# blink1mk3_micro1c.net
KiCad netlist of a schematic drawn in EAGLE
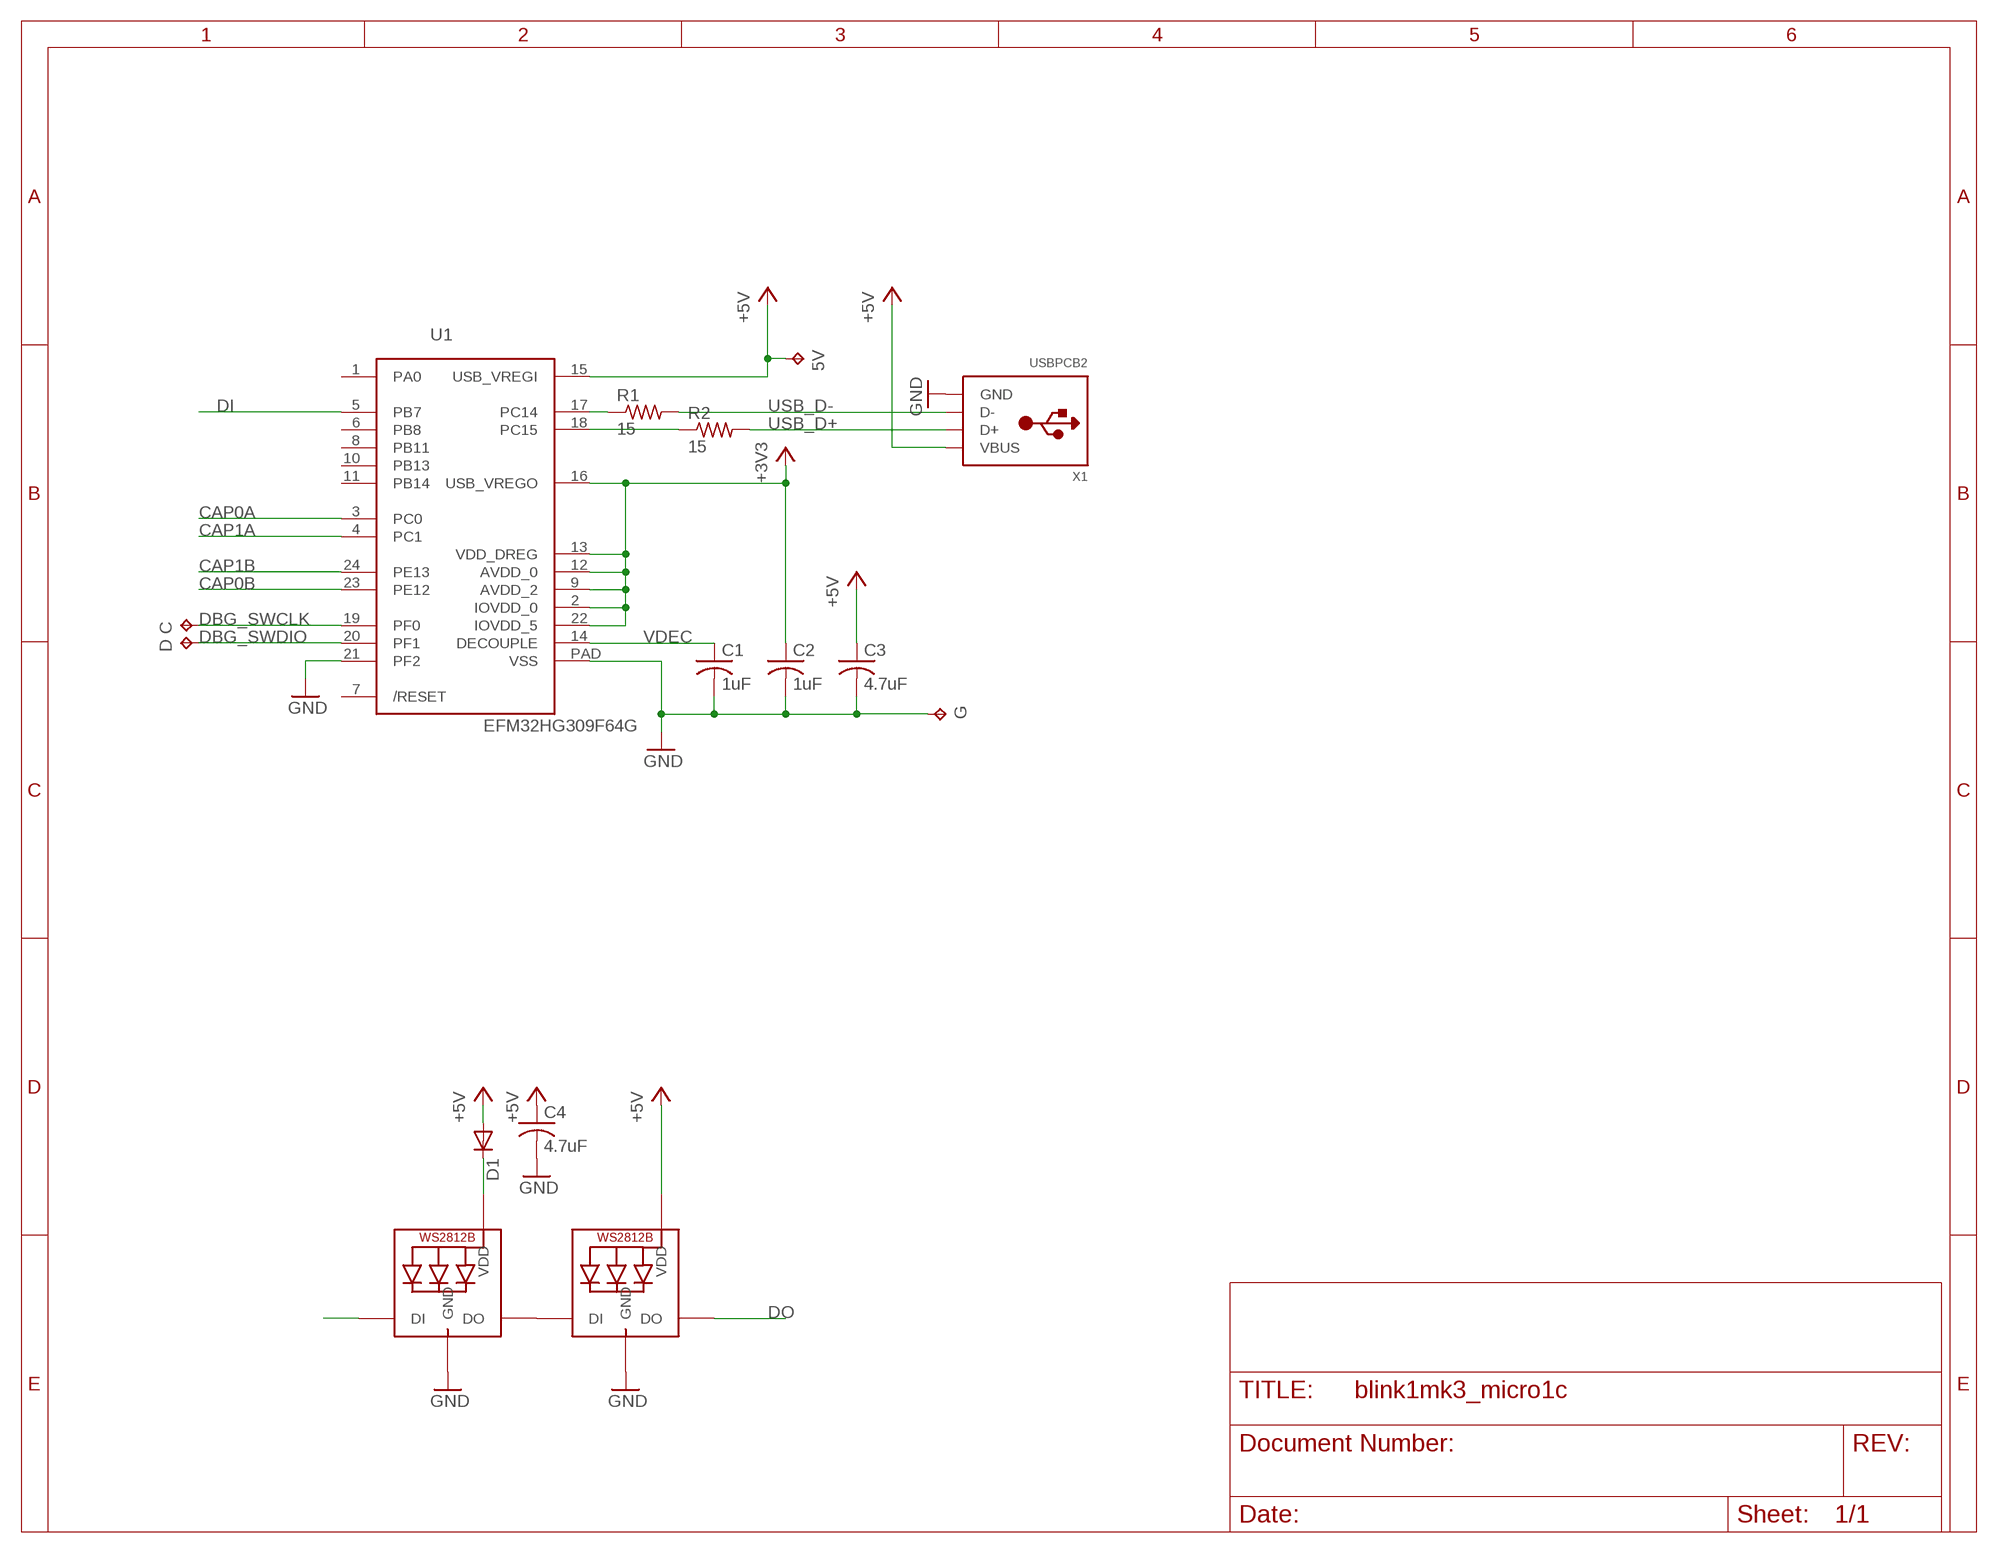
[diagram p0: schematic, sheet 1]

(export (version "E")
  (design (tool "Eeschema 10.0.6"))
  (components
    (comp (ref "5V")
      (value "TPTP10R")
      (footprint "eagle-import:TP10R")
      (libsource (lib "eagle-import") (part "TPTP10R"))
    )
    (comp (ref "C")
      (value "TPTP10R")
      (footprint "eagle-import:TP10R")
      (libsource (lib "eagle-import") (part "TPTP10R"))
    )
    (comp (ref "C1")
      (value "1uF")
      (footprint "eagle-import:C0402")
      (libsource (lib "eagle-import") (part "C-USC0402"))
    )
    (comp (ref "C2")
      (value "1uF")
      (footprint "eagle-import:C0402")
      (libsource (lib "eagle-import") (part "C-USC0402"))
    )
    (comp (ref "C3")
      (value "4.7uF")
      (footprint "eagle-import:C0402")
      (libsource (lib "eagle-import") (part "C-USC0402"))
    )
    (comp (ref "C4")
      (value "4.7uF")
      (footprint "eagle-import:C0402")
      (libsource (lib "eagle-import") (part "C-USC0402"))
    )
    (comp (ref "D")
      (value "TPTP10R")
      (footprint "eagle-import:TP10R")
      (libsource (lib "eagle-import") (part "TPTP10R"))
    )
    (comp (ref "D1")
      (value "DIODE-SOD523")
      (footprint "eagle-import:SOD523")
      (libsource (lib "eagle-import") (part "DIODE-SOD523"))
    )
    (comp (ref "G")
      (value "TPTP10SQ")
      (footprint "eagle-import:TP10SQ")
      (libsource (lib "eagle-import") (part "TPTP10SQ"))
    )
    (comp (ref "LED1")
      (value "WS2812B4020SIDE")
      (footprint "eagle-import:SK6812-SIDE")
      (libsource (lib "eagle-import") (part "WS2812B4020SIDE"))
    )
    (comp (ref "LED2")
      (value "WS2812B4020SIDE")
      (footprint "eagle-import:SK6812-SIDE")
      (libsource (lib "eagle-import") (part "WS2812B4020SIDE"))
    )
    (comp (ref "R1")
      (value "15")
      (footprint "eagle-import:R0402")
      (libsource (lib "eagle-import") (part "R-US_R0402"))
    )
    (comp (ref "R2")
      (value "15")
      (footprint "eagle-import:R0402")
      (libsource (lib "eagle-import") (part "R-US_R0402"))
    )
    (comp (ref "U1")
      (value "EFM32HG309F64G")
      (footprint "eagle-import:QFN24PAD")
      (libsource (lib "eagle-import") (part "EFM32HG309F64G"))
    )
    (comp (ref "X1")
      (value "USBPCB2")
      (footprint "eagle-import:USB-A-PCB-2")
      (libsource (lib "eagle-import") (part "USBPCB2"))
    )
  )
  (nets
    (net (code "1") (name "+3V3") (class "Default")
      (node (ref "C2") (pin "1") (pinfunction "1_1") (pintype "passive"))
      (node (ref "U1") (pin "12") (pinfunction "AVDD_0_12") (pintype "bidirectional"))
      (node (ref "U1") (pin "13") (pinfunction "VDD_DREG_13") (pintype "bidirectional"))
      (node (ref "U1") (pin "16") (pinfunction "USB_VREGO_16") (pintype "bidirectional"))
      (node (ref "U1") (pin "2") (pinfunction "IOVDD_0_2") (pintype "bidirectional"))
      (node (ref "U1") (pin "22") (pinfunction "IOVDD_5_22") (pintype "bidirectional"))
      (node (ref "U1") (pin "9") (pinfunction "AVDD_2_9") (pintype "bidirectional"))
    )
    (net (code "2") (name "+5V") (class "Default")
      (node (ref "5V") (pin "TP") (pinfunction "TP_TP") (pintype "input"))
      (node (ref "C3") (pin "1") (pinfunction "1_1") (pintype "passive"))
      (node (ref "C4") (pin "1") (pinfunction "1_1") (pintype "passive"))
      (node (ref "D1") (pin "A") (pinfunction "A_A") (pintype "passive"))
      (node (ref "LED2") (pin "1-VDD") (pinfunction "VDD_1-VDD") (pintype "power_in"))
      (node (ref "U1") (pin "15") (pinfunction "USB_VREGI_15") (pintype "bidirectional"))
      (node (ref "X1") (pin "5V") (pinfunction "VBUS_5V") (pintype "power_in"))
    )
    (net (code "3") (name "/CAP0A") (class "Default")
      (node (ref "U1") (pin "3") (pinfunction "PC0_3") (pintype "bidirectional"))
    )
    (net (code "4") (name "/CAP0B") (class "Default")
      (node (ref "U1") (pin "23") (pinfunction "PE12_23") (pintype "bidirectional"))
    )
    (net (code "5") (name "/CAP1A") (class "Default")
      (node (ref "U1") (pin "4") (pinfunction "PC1_4") (pintype "bidirectional"))
    )
    (net (code "6") (name "/CAP1B") (class "Default")
      (node (ref "U1") (pin "24") (pinfunction "PE13_24") (pintype "bidirectional"))
    )
    (net (code "7") (name "/DBG_SWCLK") (class "Default")
      (node (ref "C") (pin "TP") (pinfunction "TP_TP") (pintype "input"))
      (node (ref "U1") (pin "19") (pinfunction "PF0_19") (pintype "bidirectional"))
    )
    (net (code "8") (name "/DBG_SWDIO") (class "Default")
      (node (ref "D") (pin "TP") (pinfunction "TP_TP") (pintype "input"))
      (node (ref "U1") (pin "20") (pinfunction "PF1_20") (pintype "bidirectional"))
    )
    (net (code "9") (name "/DI") (class "Default")
      (node (ref "LED1") (pin "4-DIN") (pinfunction "DI_4-DIN") (pintype "input"))
      (node (ref "U1") (pin "5") (pinfunction "PB7_5") (pintype "bidirectional"))
    )
    (net (code "10") (name "/DO") (class "Default")
      (node (ref "LED2") (pin "2-DOUT") (pinfunction "DO_2-DOUT") (pintype "output"))
    )
    (net (code "11") (name "/USB_D+") (class "Default")
      (node (ref "R2") (pin "2") (pinfunction "2_2") (pintype "passive"))
      (node (ref "X1") (pin "USB_P") (pinfunction "D+_USB_P") (pintype "bidirectional"))
    )
    (net (code "12") (name "/USB_D-") (class "Default")
      (node (ref "R1") (pin "2") (pinfunction "2_2") (pintype "passive"))
      (node (ref "X1") (pin "USB_M") (pinfunction "D-_USB_M") (pintype "bidirectional"))
    )
    (net (code "13") (name "/VDEC") (class "Default")
      (node (ref "C1") (pin "1") (pinfunction "1_1") (pintype "passive"))
      (node (ref "U1") (pin "14") (pinfunction "DECOUPLE_14") (pintype "bidirectional"))
    )
    (net (code "14") (name "GND") (class "Default")
      (node (ref "C1") (pin "2") (pinfunction "2_2") (pintype "passive"))
      (node (ref "C2") (pin "2") (pinfunction "2_2") (pintype "passive"))
      (node (ref "C3") (pin "2") (pinfunction "2_2") (pintype "passive"))
      (node (ref "C4") (pin "2") (pinfunction "2_2") (pintype "passive"))
      (node (ref "G") (pin "TP") (pinfunction "TP_TP") (pintype "input"))
      (node (ref "LED1") (pin "3-GND") (pinfunction "GND_3-GND") (pintype "power_in"))
      (node (ref "LED2") (pin "3-GND") (pinfunction "GND_3-GND") (pintype "power_in"))
      (node (ref "U1") (pin "21") (pinfunction "PF2_21") (pintype "bidirectional"))
      (node (ref "U1") (pin "PAD") (pinfunction "VSS_PAD") (pintype "bidirectional"))
      (node (ref "X1") (pin "GND") (pinfunction "GND_GND") (pintype "power_in"))
    )
    (net (code "15") (name "Net-(LED1-DO)") (class "Default")
      (node (ref "LED1") (pin "2-DOUT") (pinfunction "DO_2-DOUT") (pintype "output"))
      (node (ref "LED2") (pin "4-DIN") (pinfunction "DI_4-DIN") (pintype "input"))
    )
    (net (code "16") (name "Net-(LED1-VDD)") (class "Default")
      (node (ref "D1") (pin "C") (pinfunction "C_C") (pintype "passive"))
      (node (ref "LED1") (pin "1-VDD") (pinfunction "VDD_1-VDD") (pintype "power_in"))
    )
    (net (code "17") (name "Net-(U1-PC14)") (class "Default")
      (node (ref "R1") (pin "1") (pinfunction "1_1") (pintype "passive"))
      (node (ref "U1") (pin "17") (pinfunction "PC14_17") (pintype "bidirectional"))
    )
    (net (code "18") (name "Net-(U1-PC15)") (class "Default")
      (node (ref "R2") (pin "1") (pinfunction "1_1") (pintype "passive"))
      (node (ref "U1") (pin "18") (pinfunction "PC15_18") (pintype "bidirectional"))
    )
    (net (code "19") (name "unconnected-(U1-PA0-Pad1)") (class "Default")
      (node (ref "U1") (pin "1") (pinfunction "PA0_1") (pintype "bidirectional"))
    )
    (net (code "20") (name "unconnected-(U1-PB8-Pad6)") (class "Default")
      (node (ref "U1") (pin "6") (pinfunction "PB8_6") (pintype "bidirectional"))
    )
    (net (code "21") (name "unconnected-(U1-PB11-Pad8)") (class "Default")
      (node (ref "U1") (pin "8") (pinfunction "PB11_8") (pintype "bidirectional"))
    )
    (net (code "22") (name "unconnected-(U1-PB13-Pad10)") (class "Default")
      (node (ref "U1") (pin "10") (pinfunction "PB13_10") (pintype "bidirectional"))
    )
    (net (code "23") (name "unconnected-(U1-PB14-Pad11)") (class "Default")
      (node (ref "U1") (pin "11") (pinfunction "PB14_11") (pintype "bidirectional"))
    )
    (net (code "24") (name "unconnected-(U1-{slash}RESET-Pad7)") (class "Default")
      (node (ref "U1") (pin "7") (pinfunction "/RESET_7") (pintype "bidirectional"))
    )
  )
)
